# GP2Y1010AU0F.net
KiCad netlist of a schematic drawn in EAGLE
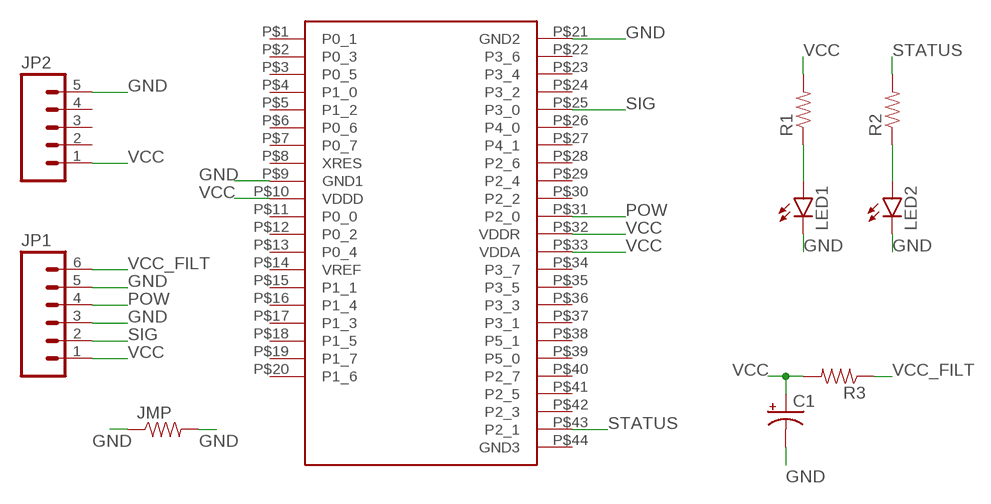
[diagram p0: schematic, sheet 1]

(export (version "E")
  (design (tool "Eeschema 10.0.6"))
  (components
    (comp (ref "C1")
      (value "CAP_POLPTH1")
      (footprint "eagle-import:CPOL-RADIAL-100UF-25V")
      (libsource (lib "eagle-import") (part "CAP_POLPTH1"))
    )
    (comp (ref "JMP")
      (value "RESISTORKIT")
      (footprint "eagle-import:AXIAL-0.3-KIT")
      (libsource (lib "eagle-import") (part "RESISTORKIT"))
    )
    (comp (ref "JP1")
      (value "M06LONGPADS")
      (footprint "eagle-import:1X06_LONGPADS")
      (libsource (lib "eagle-import") (part "M06LONGPADS"))
    )
    (comp (ref "JP2")
      (value "M05PTH_LONGPADS")
      (footprint "eagle-import:1X05_LONGPADS")
      (libsource (lib "eagle-import") (part "M05PTH_LONGPADS"))
    )
    (comp (ref "LED1")
      (value "LED3MM")
      (footprint "eagle-import:LED3MM")
      (libsource (lib "eagle-import") (part "LED3MM"))
    )
    (comp (ref "LED2")
      (value "LED3MM")
      (footprint "eagle-import:LED3MM")
      (libsource (lib "eagle-import") (part "LED3MM"))
    )
    (comp (ref "R1")
      (value "RESISTORPTH-1/4W")
      (footprint "eagle-import:AXIAL-0.4")
      (libsource (lib "eagle-import") (part "RESISTORPTH-1/4W"))
    )
    (comp (ref "R2")
      (value "RESISTORPTH-1/4W")
      (footprint "eagle-import:AXIAL-0.4")
      (libsource (lib "eagle-import") (part "RESISTORPTH-1/4W"))
    )
    (comp (ref "R3")
      (value "RESISTORPTH-1/4W")
      (footprint "eagle-import:AXIAL-0.4")
      (libsource (lib "eagle-import") (part "RESISTORPTH-1/4W"))
    )
    (comp (ref "U$1")
      (value "CYBLE_MODULE")
      (footprint "eagle-import:CYBLE_MODULE")
      (libsource (lib "eagle-import") (part "CYBLE_MODULE"))
    )
  )
  (nets
    (net (code "1") (name "/GND") (class "Default")
      (node (ref "C1") (pin "2") (pinfunction "-_2") (pintype "passive"))
      (node (ref "JMP") (pin "P$1") (pinfunction "1_P$1") (pintype "passive"))
      (node (ref "JMP") (pin "P$2") (pinfunction "2_P$2") (pintype "passive"))
      (node (ref "JP1") (pin "3") (pinfunction "3_3") (pintype "passive"))
      (node (ref "JP1") (pin "5") (pinfunction "5_5") (pintype "passive"))
      (node (ref "JP2") (pin "5") (pinfunction "5_5") (pintype "passive"))
      (node (ref "LED1") (pin "K") (pinfunction "C_K") (pintype "passive"))
      (node (ref "LED2") (pin "K") (pinfunction "C_K") (pintype "passive"))
      (node (ref "U$1") (pin "P$21") (pinfunction "GND2_P$21") (pintype "bidirectional"))
      (node (ref "U$1") (pin "P$9") (pinfunction "GND1_P$9") (pintype "bidirectional"))
    )
    (net (code "2") (name "/POW") (class "Default")
      (node (ref "JP1") (pin "4") (pinfunction "4_4") (pintype "passive"))
      (node (ref "U$1") (pin "P$31") (pinfunction "P2_0_P$31") (pintype "bidirectional"))
    )
    (net (code "3") (name "/SIG") (class "Default")
      (node (ref "JP1") (pin "2") (pinfunction "2_2") (pintype "passive"))
      (node (ref "U$1") (pin "P$25") (pinfunction "P3_0_P$25") (pintype "bidirectional"))
    )
    (net (code "4") (name "/STATUS") (class "Default")
      (node (ref "R2") (pin "P$2") (pinfunction "2_P$2") (pintype "passive"))
      (node (ref "U$1") (pin "P$43") (pinfunction "P2_1_P$43") (pintype "bidirectional"))
    )
    (net (code "5") (name "/VCC") (class "Default")
      (node (ref "C1") (pin "1") (pinfunction "+_1") (pintype "passive"))
      (node (ref "JP1") (pin "1") (pinfunction "1_1") (pintype "passive"))
      (node (ref "JP2") (pin "1") (pinfunction "1_1") (pintype "passive"))
      (node (ref "R1") (pin "P$2") (pinfunction "2_P$2") (pintype "passive"))
      (node (ref "R3") (pin "P$2") (pinfunction "2_P$2") (pintype "passive"))
      (node (ref "U$1") (pin "P$10") (pinfunction "VDDD_P$10") (pintype "bidirectional"))
      (node (ref "U$1") (pin "P$32") (pinfunction "VDDR_P$32") (pintype "bidirectional"))
      (node (ref "U$1") (pin "P$33") (pinfunction "VDDA_P$33") (pintype "bidirectional"))
    )
    (net (code "6") (name "/VCC_FILT") (class "Default")
      (node (ref "JP1") (pin "6") (pinfunction "6_6") (pintype "passive"))
      (node (ref "R3") (pin "P$1") (pinfunction "1_P$1") (pintype "passive"))
    )
    (net (code "7") (name "Net-(R1-1)") (class "Default")
      (node (ref "LED1") (pin "A") (pinfunction "A_A") (pintype "passive"))
      (node (ref "R1") (pin "P$1") (pinfunction "1_P$1") (pintype "passive"))
    )
    (net (code "8") (name "Net-(R2-1)") (class "Default")
      (node (ref "LED2") (pin "A") (pinfunction "A_A") (pintype "passive"))
      (node (ref "R2") (pin "P$1") (pinfunction "1_P$1") (pintype "passive"))
    )
    (net (code "9") (name "unconnected-(JP2-Pad2)") (class "Default")
      (node (ref "JP2") (pin "2") (pinfunction "2_2") (pintype "passive"))
    )
    (net (code "10") (name "unconnected-(JP2-Pad3)") (class "Default")
      (node (ref "JP2") (pin "3") (pinfunction "3_3") (pintype "passive"))
    )
    (net (code "11") (name "unconnected-(JP2-Pad4)") (class "Default")
      (node (ref "JP2") (pin "4") (pinfunction "4_4") (pintype "passive"))
    )
    (net (code "12") (name "unconnected-(U$1-GND3-PadP$44)") (class "Default")
      (node (ref "U$1") (pin "P$44") (pinfunction "GND3_P$44") (pintype "bidirectional"))
    )
    (net (code "13") (name "unconnected-(U$1-P0_0-PadP$11)") (class "Default")
      (node (ref "U$1") (pin "P$11") (pinfunction "P0_0_P$11") (pintype "bidirectional"))
    )
    (net (code "14") (name "unconnected-(U$1-P0_1-PadP$1)") (class "Default")
      (node (ref "U$1") (pin "P$1") (pinfunction "P0_1_P$1") (pintype "bidirectional"))
    )
    (net (code "15") (name "unconnected-(U$1-P0_2-PadP$12)") (class "Default")
      (node (ref "U$1") (pin "P$12") (pinfunction "P0_2_P$12") (pintype "bidirectional"))
    )
    (net (code "16") (name "unconnected-(U$1-P0_3-PadP$2)") (class "Default")
      (node (ref "U$1") (pin "P$2") (pinfunction "P0_3_P$2") (pintype "bidirectional"))
    )
    (net (code "17") (name "unconnected-(U$1-P0_4-PadP$13)") (class "Default")
      (node (ref "U$1") (pin "P$13") (pinfunction "P0_4_P$13") (pintype "bidirectional"))
    )
    (net (code "18") (name "unconnected-(U$1-P0_5-PadP$3)") (class "Default")
      (node (ref "U$1") (pin "P$3") (pinfunction "P0_5_P$3") (pintype "bidirectional"))
    )
    (net (code "19") (name "unconnected-(U$1-P0_6-PadP$6)") (class "Default")
      (node (ref "U$1") (pin "P$6") (pinfunction "P0_6_P$6") (pintype "bidirectional"))
    )
    (net (code "20") (name "unconnected-(U$1-P0_7-PadP$7)") (class "Default")
      (node (ref "U$1") (pin "P$7") (pinfunction "P0_7_P$7") (pintype "bidirectional"))
    )
    (net (code "21") (name "unconnected-(U$1-P1_0-PadP$4)") (class "Default")
      (node (ref "U$1") (pin "P$4") (pinfunction "P1_0_P$4") (pintype "bidirectional"))
    )
    (net (code "22") (name "unconnected-(U$1-P1_1-PadP$15)") (class "Default")
      (node (ref "U$1") (pin "P$15") (pinfunction "P1_1_P$15") (pintype "bidirectional"))
    )
    (net (code "23") (name "unconnected-(U$1-P1_2-PadP$5)") (class "Default")
      (node (ref "U$1") (pin "P$5") (pinfunction "P1_2_P$5") (pintype "bidirectional"))
    )
    (net (code "24") (name "unconnected-(U$1-P1_3-PadP$17)") (class "Default")
      (node (ref "U$1") (pin "P$17") (pinfunction "P1_3_P$17") (pintype "bidirectional"))
    )
    (net (code "25") (name "unconnected-(U$1-P1_4-PadP$16)") (class "Default")
      (node (ref "U$1") (pin "P$16") (pinfunction "P1_4_P$16") (pintype "bidirectional"))
    )
    (net (code "26") (name "unconnected-(U$1-P1_5-PadP$18)") (class "Default")
      (node (ref "U$1") (pin "P$18") (pinfunction "P1_5_P$18") (pintype "bidirectional"))
    )
    (net (code "27") (name "unconnected-(U$1-P1_6-PadP$20)") (class "Default")
      (node (ref "U$1") (pin "P$20") (pinfunction "P1_6_P$20") (pintype "bidirectional"))
    )
    (net (code "28") (name "unconnected-(U$1-P1_7-PadP$19)") (class "Default")
      (node (ref "U$1") (pin "P$19") (pinfunction "P1_7_P$19") (pintype "bidirectional"))
    )
    (net (code "29") (name "unconnected-(U$1-P2_2-PadP$30)") (class "Default")
      (node (ref "U$1") (pin "P$30") (pinfunction "P2_2_P$30") (pintype "bidirectional"))
    )
    (net (code "30") (name "unconnected-(U$1-P2_3-PadP$42)") (class "Default")
      (node (ref "U$1") (pin "P$42") (pinfunction "P2_3_P$42") (pintype "bidirectional"))
    )
    (net (code "31") (name "unconnected-(U$1-P2_4-PadP$29)") (class "Default")
      (node (ref "U$1") (pin "P$29") (pinfunction "P2_4_P$29") (pintype "bidirectional"))
    )
    (net (code "32") (name "unconnected-(U$1-P2_5-PadP$41)") (class "Default")
      (node (ref "U$1") (pin "P$41") (pinfunction "P2_5_P$41") (pintype "bidirectional"))
    )
    (net (code "33") (name "unconnected-(U$1-P2_6-PadP$28)") (class "Default")
      (node (ref "U$1") (pin "P$28") (pinfunction "P2_6_P$28") (pintype "bidirectional"))
    )
    (net (code "34") (name "unconnected-(U$1-P2_7-PadP$40)") (class "Default")
      (node (ref "U$1") (pin "P$40") (pinfunction "P2_7_P$40") (pintype "bidirectional"))
    )
    (net (code "35") (name "unconnected-(U$1-P3_1-PadP$37)") (class "Default")
      (node (ref "U$1") (pin "P$37") (pinfunction "P3_1_P$37") (pintype "bidirectional"))
    )
    (net (code "36") (name "unconnected-(U$1-P3_2-PadP$24)") (class "Default")
      (node (ref "U$1") (pin "P$24") (pinfunction "P3_2_P$24") (pintype "bidirectional"))
    )
    (net (code "37") (name "unconnected-(U$1-P3_3-PadP$36)") (class "Default")
      (node (ref "U$1") (pin "P$36") (pinfunction "P3_3_P$36") (pintype "bidirectional"))
    )
    (net (code "38") (name "unconnected-(U$1-P3_4-PadP$23)") (class "Default")
      (node (ref "U$1") (pin "P$23") (pinfunction "P3_4_P$23") (pintype "bidirectional"))
    )
    (net (code "39") (name "unconnected-(U$1-P3_5-PadP$35)") (class "Default")
      (node (ref "U$1") (pin "P$35") (pinfunction "P3_5_P$35") (pintype "bidirectional"))
    )
    (net (code "40") (name "unconnected-(U$1-P3_6-PadP$22)") (class "Default")
      (node (ref "U$1") (pin "P$22") (pinfunction "P3_6_P$22") (pintype "bidirectional"))
    )
    (net (code "41") (name "unconnected-(U$1-P3_7-PadP$34)") (class "Default")
      (node (ref "U$1") (pin "P$34") (pinfunction "P3_7_P$34") (pintype "bidirectional"))
    )
    (net (code "42") (name "unconnected-(U$1-P4_0-PadP$26)") (class "Default")
      (node (ref "U$1") (pin "P$26") (pinfunction "P4_0_P$26") (pintype "bidirectional"))
    )
    (net (code "43") (name "unconnected-(U$1-P4_1-PadP$27)") (class "Default")
      (node (ref "U$1") (pin "P$27") (pinfunction "P4_1_P$27") (pintype "bidirectional"))
    )
    (net (code "44") (name "unconnected-(U$1-P5_0-PadP$39)") (class "Default")
      (node (ref "U$1") (pin "P$39") (pinfunction "P5_0_P$39") (pintype "bidirectional"))
    )
    (net (code "45") (name "unconnected-(U$1-P5_1-PadP$38)") (class "Default")
      (node (ref "U$1") (pin "P$38") (pinfunction "P5_1_P$38") (pintype "bidirectional"))
    )
    (net (code "46") (name "unconnected-(U$1-VREF-PadP$14)") (class "Default")
      (node (ref "U$1") (pin "P$14") (pinfunction "VREF_P$14") (pintype "bidirectional"))
    )
    (net (code "47") (name "unconnected-(U$1-XRES-PadP$8)") (class "Default")
      (node (ref "U$1") (pin "P$8") (pinfunction "XRES_P$8") (pintype "bidirectional"))
    )
  )
)
